# SCH_Basis.net
KiCad netlist of a schematic drawn in EAGLE
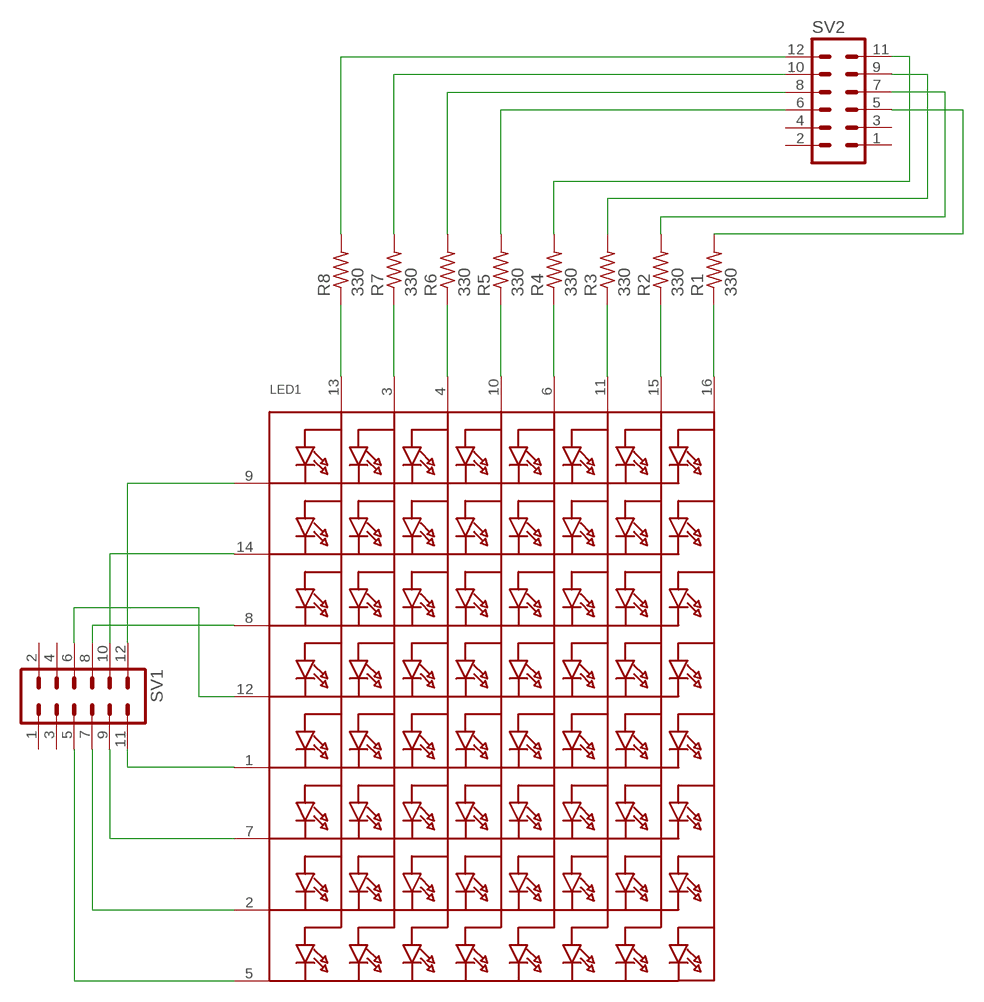
[diagram p0: schematic, sheet 1]

(export (version "E")
  (design (tool "Eeschema 10.0.6"))
  (components
    (comp (ref "LED1")
      (value "SEGMENT_8X8_ROWCATHODEM12A881UR")
      (footprint "eagle-import:SEGMENT_BL-M12A881UR")
      (libsource (lib "eagle-import") (part "SEGMENT_8X8_ROWCATHODEM12A881UR"))
    )
    (comp (ref "R1")
      (value "330")
      (footprint "eagle-import:0207_9")
      (libsource (lib "eagle-import") (part "R-US_0207/9"))
    )
    (comp (ref "R2")
      (value "330")
      (footprint "eagle-import:0207_9")
      (libsource (lib "eagle-import") (part "R-US_0207/9"))
    )
    (comp (ref "R3")
      (value "330")
      (footprint "eagle-import:0207_9")
      (libsource (lib "eagle-import") (part "R-US_0207/9"))
    )
    (comp (ref "R4")
      (value "330")
      (footprint "eagle-import:0207_9")
      (libsource (lib "eagle-import") (part "R-US_0207/9"))
    )
    (comp (ref "R5")
      (value "330")
      (footprint "eagle-import:0207_9")
      (libsource (lib "eagle-import") (part "R-US_0207/9"))
    )
    (comp (ref "R6")
      (value "330")
      (footprint "eagle-import:0207_9")
      (libsource (lib "eagle-import") (part "R-US_0207/9"))
    )
    (comp (ref "R7")
      (value "330")
      (footprint "eagle-import:0207_9")
      (libsource (lib "eagle-import") (part "R-US_0207/9"))
    )
    (comp (ref "R8")
      (value "330")
      (footprint "eagle-import:0207_9")
      (libsource (lib "eagle-import") (part "R-US_0207/9"))
    )
    (comp (ref "SV1")
      (value "MA06-2")
      (footprint "eagle-import:MA06-2")
      (libsource (lib "eagle-import") (part "MA06-2"))
    )
    (comp (ref "SV2")
      (value "MA06-2")
      (footprint "eagle-import:MA06-2")
      (libsource (lib "eagle-import") (part "MA06-2"))
    )
  )
  (nets
    (net (code "1") (name "Net-(LED1-A1)") (class "Default")
      (node (ref "LED1") (pin "13") (pinfunction "A1_13") (pintype "bidirectional"))
      (node (ref "R8") (pin "1") (pinfunction "1_1") (pintype "passive"))
    )
    (net (code "2") (name "Net-(LED1-A2)") (class "Default")
      (node (ref "LED1") (pin "3") (pinfunction "A2_3") (pintype "bidirectional"))
      (node (ref "R7") (pin "1") (pinfunction "1_1") (pintype "passive"))
    )
    (net (code "3") (name "Net-(LED1-A3)") (class "Default")
      (node (ref "LED1") (pin "4") (pinfunction "A3_4") (pintype "bidirectional"))
      (node (ref "R6") (pin "1") (pinfunction "1_1") (pintype "passive"))
    )
    (net (code "4") (name "Net-(LED1-A4)") (class "Default")
      (node (ref "LED1") (pin "10") (pinfunction "A4_10") (pintype "bidirectional"))
      (node (ref "R5") (pin "1") (pinfunction "1_1") (pintype "passive"))
    )
    (net (code "5") (name "Net-(LED1-A5)") (class "Default")
      (node (ref "LED1") (pin "6") (pinfunction "A5_6") (pintype "bidirectional"))
      (node (ref "R4") (pin "1") (pinfunction "1_1") (pintype "passive"))
    )
    (net (code "6") (name "Net-(LED1-A6)") (class "Default")
      (node (ref "LED1") (pin "11") (pinfunction "A6_11") (pintype "bidirectional"))
      (node (ref "R3") (pin "1") (pinfunction "1_1") (pintype "passive"))
    )
    (net (code "7") (name "Net-(LED1-A7)") (class "Default")
      (node (ref "LED1") (pin "15") (pinfunction "A7_15") (pintype "bidirectional"))
      (node (ref "R2") (pin "1") (pinfunction "1_1") (pintype "passive"))
    )
    (net (code "8") (name "Net-(LED1-A8)") (class "Default")
      (node (ref "LED1") (pin "16") (pinfunction "A8_16") (pintype "bidirectional"))
      (node (ref "R1") (pin "1") (pinfunction "1_1") (pintype "passive"))
    )
    (net (code "9") (name "Net-(LED1-K1)") (class "Default")
      (node (ref "LED1") (pin "9") (pinfunction "K1_9") (pintype "bidirectional"))
      (node (ref "SV1") (pin "12") (pinfunction "12_12") (pintype "passive"))
    )
    (net (code "10") (name "Net-(LED1-K2)") (class "Default")
      (node (ref "LED1") (pin "14") (pinfunction "K2_14") (pintype "bidirectional"))
      (node (ref "SV1") (pin "10") (pinfunction "10_10") (pintype "passive"))
    )
    (net (code "11") (name "Net-(LED1-K3)") (class "Default")
      (node (ref "LED1") (pin "8") (pinfunction "K3_8") (pintype "bidirectional"))
      (node (ref "SV1") (pin "8") (pinfunction "8_8") (pintype "passive"))
    )
    (net (code "12") (name "Net-(LED1-K4)") (class "Default")
      (node (ref "LED1") (pin "12") (pinfunction "K4_12") (pintype "bidirectional"))
      (node (ref "SV1") (pin "6") (pinfunction "6_6") (pintype "passive"))
    )
    (net (code "13") (name "Net-(LED1-K5)") (class "Default")
      (node (ref "LED1") (pin "1") (pinfunction "K5_1") (pintype "bidirectional"))
      (node (ref "SV1") (pin "11") (pinfunction "11_11") (pintype "passive"))
    )
    (net (code "14") (name "Net-(LED1-K6)") (class "Default")
      (node (ref "LED1") (pin "7") (pinfunction "K6_7") (pintype "bidirectional"))
      (node (ref "SV1") (pin "9") (pinfunction "9_9") (pintype "passive"))
    )
    (net (code "15") (name "Net-(LED1-K7)") (class "Default")
      (node (ref "LED1") (pin "2") (pinfunction "K7_2") (pintype "bidirectional"))
      (node (ref "SV1") (pin "7") (pinfunction "7_7") (pintype "passive"))
    )
    (net (code "16") (name "Net-(LED1-K8)") (class "Default")
      (node (ref "LED1") (pin "5") (pinfunction "K8_5") (pintype "bidirectional"))
      (node (ref "SV1") (pin "5") (pinfunction "5_5") (pintype "passive"))
    )
    (net (code "17") (name "Net-(R1-Pad2)") (class "Default")
      (node (ref "R1") (pin "2") (pinfunction "2_2") (pintype "passive"))
      (node (ref "SV2") (pin "5") (pinfunction "5_5") (pintype "passive"))
    )
    (net (code "18") (name "Net-(R2-Pad2)") (class "Default")
      (node (ref "R2") (pin "2") (pinfunction "2_2") (pintype "passive"))
      (node (ref "SV2") (pin "7") (pinfunction "7_7") (pintype "passive"))
    )
    (net (code "19") (name "Net-(R3-Pad2)") (class "Default")
      (node (ref "R3") (pin "2") (pinfunction "2_2") (pintype "passive"))
      (node (ref "SV2") (pin "9") (pinfunction "9_9") (pintype "passive"))
    )
    (net (code "20") (name "Net-(R4-Pad2)") (class "Default")
      (node (ref "R4") (pin "2") (pinfunction "2_2") (pintype "passive"))
      (node (ref "SV2") (pin "11") (pinfunction "11_11") (pintype "passive"))
    )
    (net (code "21") (name "Net-(R5-Pad2)") (class "Default")
      (node (ref "R5") (pin "2") (pinfunction "2_2") (pintype "passive"))
      (node (ref "SV2") (pin "6") (pinfunction "6_6") (pintype "passive"))
    )
    (net (code "22") (name "Net-(R6-Pad2)") (class "Default")
      (node (ref "R6") (pin "2") (pinfunction "2_2") (pintype "passive"))
      (node (ref "SV2") (pin "8") (pinfunction "8_8") (pintype "passive"))
    )
    (net (code "23") (name "Net-(R7-Pad2)") (class "Default")
      (node (ref "R7") (pin "2") (pinfunction "2_2") (pintype "passive"))
      (node (ref "SV2") (pin "10") (pinfunction "10_10") (pintype "passive"))
    )
    (net (code "24") (name "Net-(R8-Pad2)") (class "Default")
      (node (ref "R8") (pin "2") (pinfunction "2_2") (pintype "passive"))
      (node (ref "SV2") (pin "12") (pinfunction "12_12") (pintype "passive"))
    )
    (net (code "25") (name "unconnected-(SV1-Pad1)") (class "Default")
      (node (ref "SV1") (pin "1") (pinfunction "1_1") (pintype "passive"))
    )
    (net (code "26") (name "unconnected-(SV1-Pad2)") (class "Default")
      (node (ref "SV1") (pin "2") (pinfunction "2_2") (pintype "passive"))
    )
    (net (code "27") (name "unconnected-(SV1-Pad3)") (class "Default")
      (node (ref "SV1") (pin "3") (pinfunction "3_3") (pintype "passive"))
    )
    (net (code "28") (name "unconnected-(SV1-Pad4)") (class "Default")
      (node (ref "SV1") (pin "4") (pinfunction "4_4") (pintype "passive"))
    )
    (net (code "29") (name "unconnected-(SV2-Pad1)") (class "Default")
      (node (ref "SV2") (pin "1") (pinfunction "1_1") (pintype "passive"))
    )
    (net (code "30") (name "unconnected-(SV2-Pad2)") (class "Default")
      (node (ref "SV2") (pin "2") (pinfunction "2_2") (pintype "passive"))
    )
    (net (code "31") (name "unconnected-(SV2-Pad3)") (class "Default")
      (node (ref "SV2") (pin "3") (pinfunction "3_3") (pintype "passive"))
    )
    (net (code "32") (name "unconnected-(SV2-Pad4)") (class "Default")
      (node (ref "SV2") (pin "4") (pinfunction "4_4") (pintype "passive"))
    )
  )
)
